# alimenta_ao3.net
KiCad netlist of a schematic drawn in EAGLE
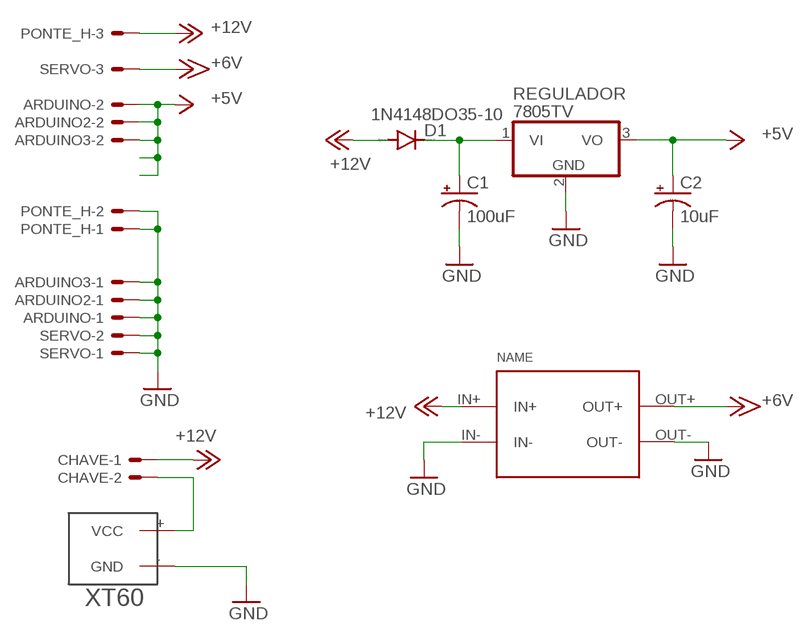
[diagram p0: schematic, sheet 1]

(export (version "E")
  (design (tool "Eeschema 10.0.6"))
  (components
    (comp (ref "ARDUINO")
      (value "KK-156-2")
      (footprint "eagle-import:KK-156-2")
      (fields (field (name "MF") "MOLEX"))
      (libsource (lib "eagle-import") (part "KK-156-2"))
    )
    (comp (ref "ARDUINO2")
      (value "KK-156-2")
      (footprint "eagle-import:KK-156-2")
      (fields (field (name "MF") "MOLEX"))
      (libsource (lib "eagle-import") (part "KK-156-2"))
    )
    (comp (ref "ARDUINO3")
      (value "KK-156-2")
      (footprint "eagle-import:KK-156-2")
      (fields (field (name "MF") "MOLEX"))
      (libsource (lib "eagle-import") (part "KK-156-2"))
    )
    (comp (ref "BUCK")
      (value "CP8-ADJ")
      (footprint "eagle-import:CP8-ADJ")
      (libsource (lib "eagle-import") (part "CP8-ADJ"))
    )
    (comp (ref "C1")
      (value "100uF")
      (footprint "eagle-import:E5-4")
      (libsource (lib "eagle-import") (part "CPOL-USE5-4"))
    )
    (comp (ref "C2")
      (value "10uF")
      (footprint "eagle-import:E5-4")
      (libsource (lib "eagle-import") (part "CPOL-USE5-4"))
    )
    (comp (ref "CHAVE")
      (value "KK-156-2")
      (footprint "eagle-import:KK-156-2")
      (fields (field (name "MF") "MOLEX"))
      (libsource (lib "eagle-import") (part "KK-156-2"))
    )
    (comp (ref "D1")
      (value "1N4148DO35-10")
      (footprint "eagle-import:DO35-10")
      (libsource (lib "eagle-import") (part "1N4148DO35-10"))
    )
    (comp (ref "PONTE_H")
      (value "KK-156-3")
      (footprint "eagle-import:KK-156-3")
      (fields (field (name "MF") "MOLEX"))
      (libsource (lib "eagle-import") (part "KK-156-3"))
    )
    (comp (ref "REGULADOR")
      (value "7805TV")
      (footprint "eagle-import:TO220V")
      (libsource (lib "eagle-import") (part "78TV05"))
    )
    (comp (ref "SERVO")
      (value "KK-156-3")
      (footprint "eagle-import:KK-156-3")
      (fields (field (name "MF") "MOLEX"))
      (libsource (lib "eagle-import") (part "KK-156-3"))
    )
    (comp (ref "U$1")
      (value "XT60")
      (footprint "eagle-import:XT60")
      (libsource (lib "eagle-import") (part "XT60"))
    )
  )
  (nets
    (net (code "1") (name "+5V") (class "Default")
      (node (ref "ARDUINO") (pin "2") (pinfunction "S_2") (pintype "passive"))
      (node (ref "ARDUINO2") (pin "2") (pinfunction "S_2") (pintype "passive"))
      (node (ref "ARDUINO3") (pin "2") (pinfunction "S_2") (pintype "passive"))
      (node (ref "C2") (pin "+") (pinfunction "+_+") (pintype "passive"))
      (node (ref "REGULADOR") (pin "3") (pinfunction "VO_3") (pintype "passive"))
    )
    (net (code "2") (name "+6V") (class "Default")
      (node (ref "BUCK") (pin "OUT+") (pinfunction "OUT+_OUT+") (pintype "passive"))
      (node (ref "SERVO") (pin "3") (pinfunction "S_3") (pintype "passive"))
    )
    (net (code "3") (name "+12V") (class "Default")
      (node (ref "BUCK") (pin "IN+") (pinfunction "IN+_IN+") (pintype "passive"))
      (node (ref "CHAVE") (pin "1") (pinfunction "S_1") (pintype "passive"))
      (node (ref "D1") (pin "A") (pinfunction "A_A") (pintype "passive"))
      (node (ref "PONTE_H") (pin "3") (pinfunction "S_3") (pintype "passive"))
    )
    (net (code "4") (name "GND") (class "Default")
      (node (ref "ARDUINO") (pin "1") (pinfunction "S_1") (pintype "passive"))
      (node (ref "ARDUINO2") (pin "1") (pinfunction "S_1") (pintype "passive"))
      (node (ref "ARDUINO3") (pin "1") (pinfunction "S_1") (pintype "passive"))
      (node (ref "BUCK") (pin "IN-") (pinfunction "IN-_IN-") (pintype "passive"))
      (node (ref "BUCK") (pin "OUT-") (pinfunction "OUT-_OUT-") (pintype "passive"))
      (node (ref "C1") (pin "-") (pinfunction "-_-") (pintype "passive"))
      (node (ref "C2") (pin "-") (pinfunction "-_-") (pintype "passive"))
      (node (ref "PONTE_H") (pin "1") (pinfunction "S_1") (pintype "passive"))
      (node (ref "PONTE_H") (pin "2") (pinfunction "S_2") (pintype "passive"))
      (node (ref "REGULADOR") (pin "2") (pinfunction "GND_2") (pintype "passive"))
      (node (ref "SERVO") (pin "1") (pinfunction "S_1") (pintype "passive"))
      (node (ref "SERVO") (pin "2") (pinfunction "S_2") (pintype "passive"))
      (node (ref "U$1") (pin "-") (pinfunction "GND_-") (pintype "bidirectional"))
    )
    (net (code "5") (name "Net-(CHAVEB-S)") (class "Default")
      (node (ref "CHAVE") (pin "2") (pinfunction "S_2") (pintype "passive"))
      (node (ref "U$1") (pin "+") (pinfunction "VCC_+") (pintype "bidirectional"))
    )
    (net (code "6") (name "Net-(REGULADOR-VI)") (class "Default")
      (node (ref "C1") (pin "+") (pinfunction "+_+") (pintype "passive"))
      (node (ref "D1") (pin "C") (pinfunction "C_C") (pintype "passive"))
      (node (ref "REGULADOR") (pin "1") (pinfunction "VI_1") (pintype "input"))
    )
  )
)
